# NES_Buttons.net
KiCad netlist of a schematic drawn in EAGLE
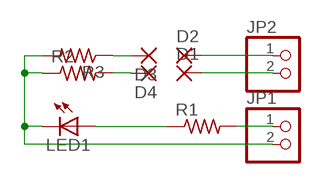
[diagram p0: schematic, sheet 1]

(export (version "E")
  (design (tool "Eeschema 10.0.6"))
  (components
    (comp (ref "D1")
      (value "2,15/1,0")
      (footprint "eagle-import:2,15_1,0")
      (libsource (lib "eagle-import") (part "2,15/1,0"))
    )
    (comp (ref "D2")
      (value "2,15/1,0")
      (footprint "eagle-import:2,15_1,0")
      (libsource (lib "eagle-import") (part "2,15/1,0"))
    )
    (comp (ref "D3")
      (value "2,15/1,0")
      (footprint "eagle-import:2,15_1,0")
      (libsource (lib "eagle-import") (part "2,15/1,0"))
    )
    (comp (ref "D4")
      (value "2,15/1,0")
      (footprint "eagle-import:2,15_1,0")
      (libsource (lib "eagle-import") (part "2,15/1,0"))
    )
    (comp (ref "JP1")
      (value "PINHD-1X2")
      (footprint "eagle-import:1X02")
      (libsource (lib "eagle-import") (part "PINHD-1X2"))
    )
    (comp (ref "JP2")
      (value "PINHD-1X2")
      (footprint "eagle-import:1X02")
      (libsource (lib "eagle-import") (part "PINHD-1X2"))
    )
    (comp (ref "LED1")
      (value "LED3MM")
      (footprint "eagle-import:LED3MM")
      (libsource (lib "eagle-import") (part "LED3MM"))
    )
    (comp (ref "R1")
      (value "R-US_R1206")
      (footprint "eagle-import:R1206")
      (libsource (lib "eagle-import") (part "R-US_R1206"))
    )
    (comp (ref "R2")
      (value "R-US_R1206")
      (footprint "eagle-import:R1206")
      (libsource (lib "eagle-import") (part "R-US_R1206"))
    )
    (comp (ref "R3")
      (value "R-US_R1206")
      (footprint "eagle-import:R1206")
      (libsource (lib "eagle-import") (part "R-US_R1206"))
    )
  )
  (nets
    (net (code "1") (name "Net-(D1-P)") (class "Default")
      (node (ref "D1") (pin "1") (pinfunction "P_1") (pintype "passive"))
      (node (ref "JP2") (pin "2") (pinfunction "2_2") (pintype "passive"))
    )
    (net (code "2") (name "Net-(D2-P)") (class "Default")
      (node (ref "D2") (pin "1") (pinfunction "P_1") (pintype "passive"))
      (node (ref "JP2") (pin "1") (pinfunction "1_1") (pintype "passive"))
    )
    (net (code "3") (name "Net-(D3-P)") (class "Default")
      (node (ref "D3") (pin "1") (pinfunction "P_1") (pintype "passive"))
      (node (ref "R3") (pin "1") (pinfunction "1_1") (pintype "passive"))
    )
    (net (code "4") (name "Net-(D4-P)") (class "Default")
      (node (ref "D4") (pin "1") (pinfunction "P_1") (pintype "passive"))
      (node (ref "R2") (pin "2") (pinfunction "2_2") (pintype "passive"))
    )
    (net (code "5") (name "Net-(JP1-Pad1)") (class "Default")
      (node (ref "JP1") (pin "1") (pinfunction "1_1") (pintype "passive"))
      (node (ref "R1") (pin "2") (pinfunction "2_2") (pintype "passive"))
    )
    (net (code "6") (name "Net-(LED1-C)") (class "Default")
      (node (ref "JP1") (pin "2") (pinfunction "2_2") (pintype "passive"))
      (node (ref "LED1") (pin "K") (pinfunction "C_K") (pintype "passive"))
      (node (ref "R2") (pin "1") (pinfunction "1_1") (pintype "passive"))
      (node (ref "R3") (pin "2") (pinfunction "2_2") (pintype "passive"))
    )
    (net (code "7") (name "Net-(LED1-PadA)") (class "Default")
      (node (ref "LED1") (pin "A") (pinfunction "A_A") (pintype "passive"))
      (node (ref "R1") (pin "1") (pinfunction "1_1") (pintype "passive"))
    )
  )
)
